# SCH_555-Chaser_2025-11-29.net
KiCad netlist of a schematic drawn in EasyEDA
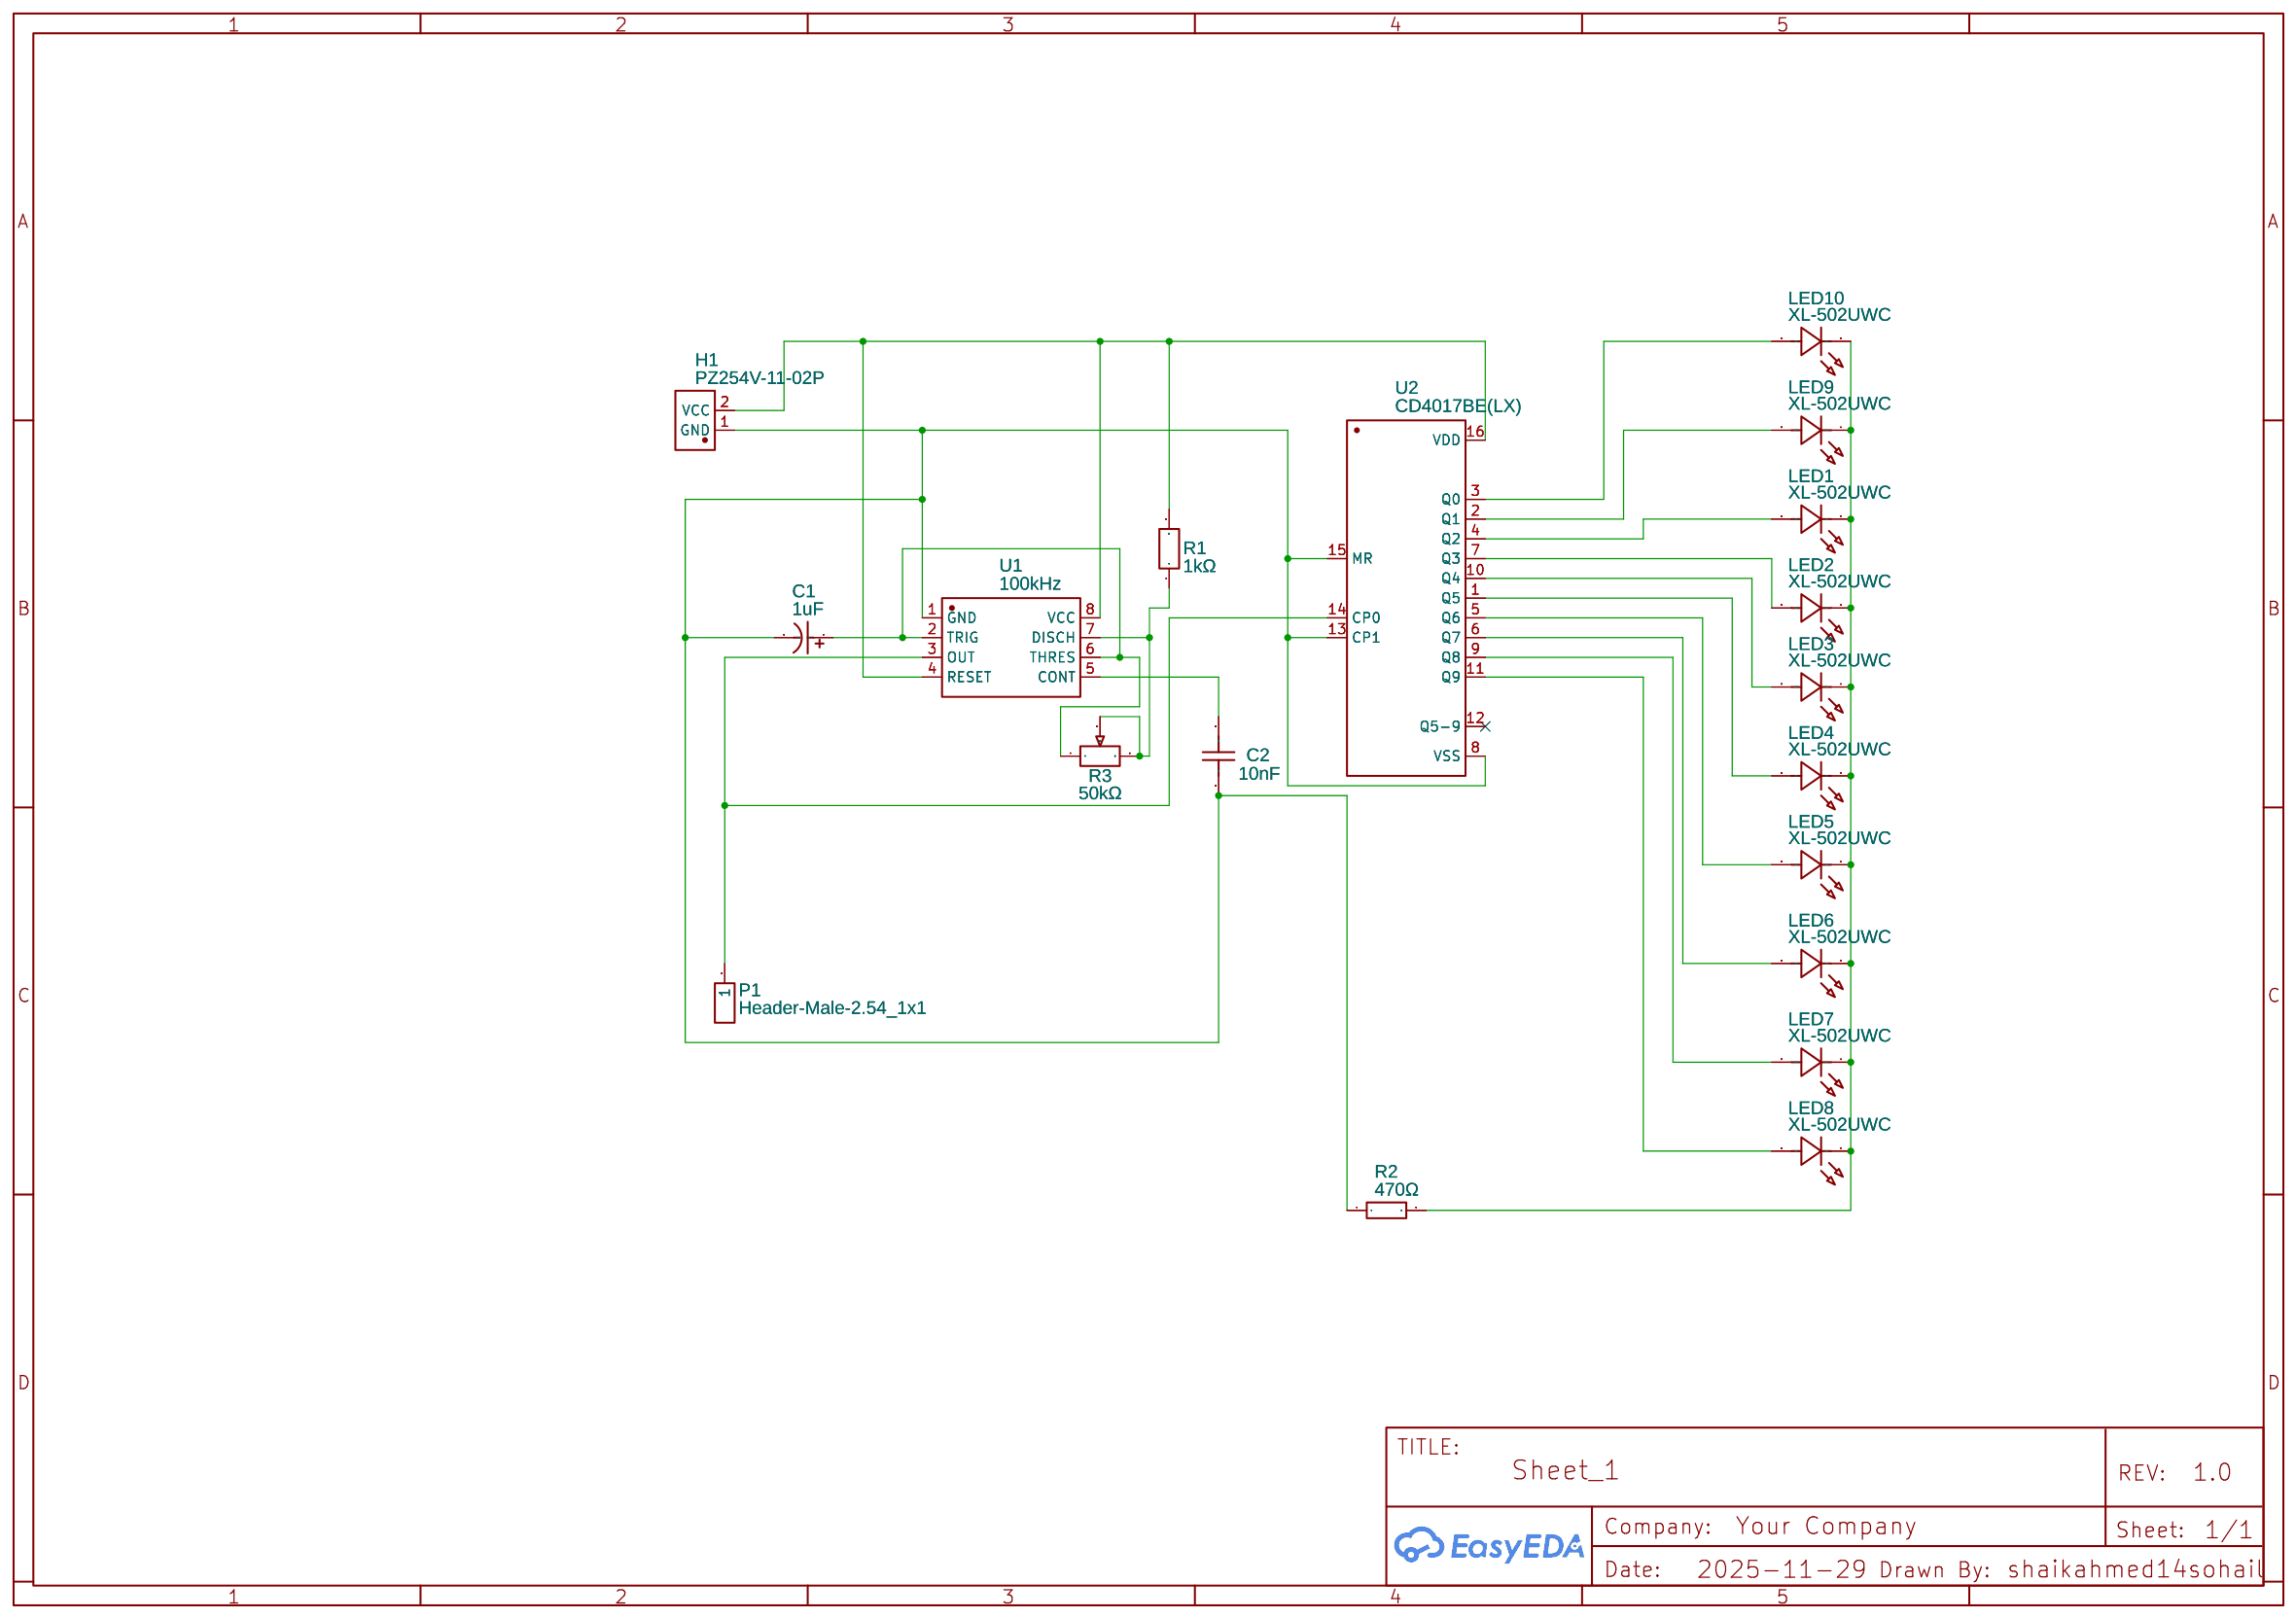
[diagram p0: schematic sheet]

(export (version "E")
  (design (tool "Eeschema 10.0.6"))
  (components
    (comp (ref "C1")
      (value "1uF")
      (fields (field (name "Manufacturer Part") "KF010M050C110A") (field (name "Manufacturer") "CapXon(丰宾)"))
      (libsource (lib "") (part "KF010M050C110A"))
    )
    (comp (ref "C2")
      (value "10nF")
      (fields (field (name "Manufacturer Part") "N09F1B103MN0B0S0N0") (field (name "Manufacturer") "STE(松田)"))
      (libsource (lib "") (part "N09F1B103MN0B0S0N0"))
    )
    (comp (ref "H1")
      (value "PZ254V-11-02P")
      (fields (field (name "Manufacturer") "XFCN(兴飞)"))
      (libsource (lib "") (part "PZ254V-11-02P"))
    )
    (comp (ref "LED1")
      (value "XL-502UWC")
      (fields (field (name "Manufacturer") "XINGLIGHT(成兴光)"))
      (libsource (lib "") (part "XL-502UWC"))
    )
    (comp (ref "LED2")
      (value "XL-502UWC")
      (fields (field (name "Manufacturer") "XINGLIGHT(成兴光)"))
      (libsource (lib "") (part "XL-502UWC"))
    )
    (comp (ref "LED3")
      (value "XL-502UWC")
      (fields (field (name "Manufacturer") "XINGLIGHT(成兴光)"))
      (libsource (lib "") (part "XL-502UWC"))
    )
    (comp (ref "LED4")
      (value "XL-502UWC")
      (fields (field (name "Manufacturer") "XINGLIGHT(成兴光)"))
      (libsource (lib "") (part "XL-502UWC"))
    )
    (comp (ref "LED5")
      (value "XL-502UWC")
      (fields (field (name "Manufacturer") "XINGLIGHT(成兴光)"))
      (libsource (lib "") (part "XL-502UWC"))
    )
    (comp (ref "LED6")
      (value "XL-502UWC")
      (fields (field (name "Manufacturer") "XINGLIGHT(成兴光)"))
      (libsource (lib "") (part "XL-502UWC"))
    )
    (comp (ref "LED7")
      (value "XL-502UWC")
      (fields (field (name "Manufacturer") "XINGLIGHT(成兴光)"))
      (libsource (lib "") (part "XL-502UWC"))
    )
    (comp (ref "LED8")
      (value "XL-502UWC")
      (fields (field (name "Manufacturer") "XINGLIGHT(成兴光)"))
      (libsource (lib "") (part "XL-502UWC"))
    )
    (comp (ref "LED9")
      (value "XL-502UWC")
      (fields (field (name "Manufacturer") "XINGLIGHT(成兴光)"))
      (libsource (lib "") (part "XL-502UWC"))
    )
    (comp (ref "LED10")
      (value "XL-502UWC")
      (fields (field (name "Manufacturer") "XINGLIGHT(成兴光)"))
      (libsource (lib "") (part "XL-502UWC"))
    )
    (comp (ref "P1")
      (value "Header-Male-2.54_1x1")
      (fields (field (name "Manufacturer Part") "2.54-1*1P针") (field (name "Manufacturer") "BOOMELE(博穆精密)"))
      (libsource (lib "") (part "Header-Male-2.54_1x1"))
    )
    (comp (ref "R1")
      (value "1kΩ")
      (fields (field (name "Manufacturer Part") "MF1/4W-1KΩ±1%T52") (field (name "Manufacturer") "华星机电"))
      (libsource (lib "") (part "MF1/4W-1KΩ±1%T52"))
    )
    (comp (ref "R2")
      (value "470Ω")
      (fields
        (field (name "Manufacturer Part") "MFR0W4F4700A50")
        (field (name "Manufacturer") "UNI-ROYAL(厚声)")
      )
      (libsource (lib "") (part "MFR0W4F4700A50"))
    )
    (comp (ref "R3")
      (value "50kΩ")
      (fields (field (name "Manufacturer Part") "3296X-1-503") (field (name "Manufacturer") "BOCHEN(博晨)"))
      (libsource (lib "") (part "3296X-1-503_C118912"))
    )
    (comp (ref "U1")
      (value "100kHz")
      (fields (field (name "Manufacturer Part") "NE555P") (field (name "Manufacturer") "TI(德州仪器)"))
      (libsource (lib "") (part "NE555P"))
    )
    (comp (ref "U2")
      (value "CD4017BE(LX)")
      (fields (field (name "Manufacturer") "LX(灵星芯微)"))
      (libsource (lib "") (part "CD4017BE(LX)"))
    )
  )
  (nets
    (net (code "1") (name "Net-(H1-GND)") (class "Default")
      (node (ref "C1") (pin "2") (pinfunction "2_2") (pintype "input"))
      (node (ref "C2") (pin "1") (pinfunction "1_1") (pintype "unspecified"))
      (node (ref "H1") (pin "1") (pinfunction "GND_1") (pintype "unspecified"))
      (node (ref "R2") (pin "1") (pinfunction "1_1") (pintype "input"))
      (node (ref "U1") (pin "1") (pinfunction "GND_1") (pintype "unspecified"))
      (node (ref "U2") (pin "13") (pinfunction "CP1_13") (pintype "unspecified"))
      (node (ref "U2") (pin "15") (pinfunction "MR_15") (pintype "unspecified"))
      (node (ref "U2") (pin "8") (pinfunction "VSS_8") (pintype "unspecified"))
    )
    (net (code "2") (name "Net-(H1-VCC)") (class "Default")
      (node (ref "H1") (pin "2") (pinfunction "VCC_2") (pintype "unspecified"))
      (node (ref "R1") (pin "2") (pinfunction "2_2") (pintype "unspecified"))
      (node (ref "U1") (pin "4") (pinfunction "RESET_4") (pintype "unspecified"))
      (node (ref "U1") (pin "8") (pinfunction "VCC_8") (pintype "unspecified"))
      (node (ref "U2") (pin "16") (pinfunction "VDD_16") (pintype "unspecified"))
    )
    (net (code "3") (name "Net-(LED1-A)") (class "Default")
      (node (ref "LED1") (pin "2") (pinfunction "A_2") (pintype "unspecified"))
      (node (ref "U2") (pin "4") (pinfunction "Q2_4") (pintype "unspecified"))
    )
    (net (code "4") (name "Net-(LED1-K)") (class "Default")
      (node (ref "LED1") (pin "1") (pinfunction "K_1") (pintype "unspecified"))
      (node (ref "LED10") (pin "1") (pinfunction "K_1") (pintype "unspecified"))
      (node (ref "LED2") (pin "1") (pinfunction "K_1") (pintype "unspecified"))
      (node (ref "LED3") (pin "1") (pinfunction "K_1") (pintype "unspecified"))
      (node (ref "LED4") (pin "1") (pinfunction "K_1") (pintype "unspecified"))
      (node (ref "LED5") (pin "1") (pinfunction "K_1") (pintype "unspecified"))
      (node (ref "LED6") (pin "1") (pinfunction "K_1") (pintype "unspecified"))
      (node (ref "LED7") (pin "1") (pinfunction "K_1") (pintype "unspecified"))
      (node (ref "LED8") (pin "1") (pinfunction "K_1") (pintype "unspecified"))
      (node (ref "LED9") (pin "1") (pinfunction "K_1") (pintype "unspecified"))
      (node (ref "R2") (pin "2") (pinfunction "2_2") (pintype "input"))
    )
    (net (code "5") (name "Net-(LED2-A)") (class "Default")
      (node (ref "LED2") (pin "2") (pinfunction "A_2") (pintype "unspecified"))
      (node (ref "U2") (pin "7") (pinfunction "Q3_7") (pintype "unspecified"))
    )
    (net (code "6") (name "Net-(LED3-A)") (class "Default")
      (node (ref "LED3") (pin "2") (pinfunction "A_2") (pintype "unspecified"))
      (node (ref "U2") (pin "10") (pinfunction "Q4_10") (pintype "unspecified"))
    )
    (net (code "7") (name "Net-(LED4-A)") (class "Default")
      (node (ref "LED4") (pin "2") (pinfunction "A_2") (pintype "unspecified"))
      (node (ref "U2") (pin "1") (pinfunction "Q5_1") (pintype "unspecified"))
    )
    (net (code "8") (name "Net-(LED5-A)") (class "Default")
      (node (ref "LED5") (pin "2") (pinfunction "A_2") (pintype "unspecified"))
      (node (ref "U2") (pin "5") (pinfunction "Q6_5") (pintype "unspecified"))
    )
    (net (code "9") (name "Net-(LED6-A)") (class "Default")
      (node (ref "LED6") (pin "2") (pinfunction "A_2") (pintype "unspecified"))
      (node (ref "U2") (pin "6") (pinfunction "Q7_6") (pintype "unspecified"))
    )
    (net (code "10") (name "Net-(LED7-A)") (class "Default")
      (node (ref "LED7") (pin "2") (pinfunction "A_2") (pintype "unspecified"))
      (node (ref "U2") (pin "9") (pinfunction "Q8_9") (pintype "unspecified"))
    )
    (net (code "11") (name "Net-(LED8-A)") (class "Default")
      (node (ref "LED8") (pin "2") (pinfunction "A_2") (pintype "unspecified"))
      (node (ref "U2") (pin "11") (pinfunction "Q9_11") (pintype "unspecified"))
    )
    (net (code "12") (name "Net-(LED9-A)") (class "Default")
      (node (ref "LED9") (pin "2") (pinfunction "A_2") (pintype "unspecified"))
      (node (ref "U2") (pin "2") (pinfunction "Q1_2") (pintype "unspecified"))
    )
    (net (code "13") (name "Net-(LED10-A)") (class "Default")
      (node (ref "LED10") (pin "2") (pinfunction "A_2") (pintype "unspecified"))
      (node (ref "U2") (pin "3") (pinfunction "Q0_3") (pintype "unspecified"))
    )
    (net (code "14") (name "Net-(U1-CONT)") (class "Default")
      (node (ref "C2") (pin "2") (pinfunction "2_2") (pintype "unspecified"))
      (node (ref "U1") (pin "5") (pinfunction "CONT_5") (pintype "unspecified"))
    )
    (net (code "15") (name "Net-(U1-DISCH)") (class "Default")
      (node (ref "R1") (pin "1") (pinfunction "1_1") (pintype "unspecified"))
      (node (ref "R3") (pin "2") (pinfunction "2_2") (pintype "input"))
      (node (ref "R3") (pin "3") (pinfunction "3_3") (pintype "input"))
      (node (ref "U1") (pin "7") (pinfunction "DISCH_7") (pintype "unspecified"))
    )
    (net (code "16") (name "Net-(U1-OUT)") (class "Default")
      (node (ref "P1") (pin "1") (pinfunction "1_1") (pintype "input"))
      (node (ref "U1") (pin "3") (pinfunction "OUT_3") (pintype "unspecified"))
      (node (ref "U2") (pin "14") (pinfunction "CP0_14") (pintype "unspecified"))
    )
    (net (code "17") (name "Net-(U1-THRES)") (class "Default")
      (node (ref "C1") (pin "1") (pinfunction "1_1") (pintype "input"))
      (node (ref "R3") (pin "1") (pinfunction "1_1") (pintype "input"))
      (node (ref "U1") (pin "2") (pinfunction "TRIG_2") (pintype "unspecified"))
      (node (ref "U1") (pin "6") (pinfunction "THRES_6") (pintype "unspecified"))
    )
    (net (code "18") (name "unconnected-(U2-Q5-9-Pad12)") (class "Default")
      (node (ref "U2") (pin "12") (pinfunction "Q5-9_12") (pintype "unspecified+no_connect"))
    )
  )
)
